# Encoder_-_error.net
KiCad netlist of a schematic drawn in Altium Designer
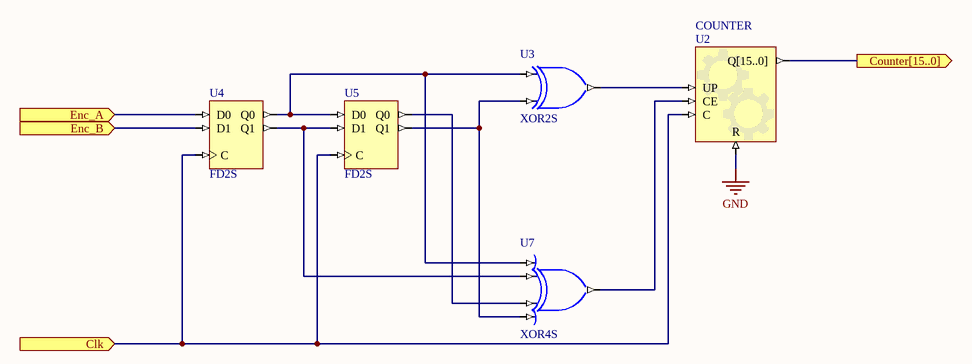
[diagram p0: Encoder - error.SchDoc]

(export (version "E")
  (design (tool "Eeschema 10.0.6"))
  (components
    (comp (ref "U2")
      (value "COUNTER")
      (description "Configurable Counter")
      (fields (field (name "PUBLISHER") "Altium Limited"))
      (libsource (lib "FPGA Configurable Generic") (part "COUNTER"))
    )
    (comp (ref "U3")
      (value "XOR2S")
      (description "2-Input Exclusive-OR Gate, Single Pin Version")
      (fields (field (name "PUBLISHER") "Altium Limited"))
      (libsource (lib "FPGA Generic") (part "XOR2S"))
    )
    (comp (ref "U4")
      (value "FD2S")
      (description "2-Bit D-Type Flip-Flop, Single Pin Version")
      (fields (field (name "PUBLISHER") "Altium Limited"))
      (libsource (lib "FPGA Generic") (part "FD2S"))
    )
    (comp (ref "U5")
      (value "FD2S")
      (description "2-Bit D-Type Flip-Flop, Single Pin Version")
      (fields (field (name "PUBLISHER") "Altium Limited"))
      (libsource (lib "FPGA Generic") (part "FD2S"))
    )
    (comp (ref "U7")
      (value "XOR4S")
      (description "4-Input Exclusive-OR Gate, Single Pin Version")
      (fields (field (name "PUBLISHER") "Altium Limited"))
      (libsource (lib "FPGA Generic") (part "XOR4S"))
    )
  )
  (nets
    (net (code "17") (name "/Clk") (class "Default")
      (node (ref "U2") (pin "C") (pinfunction "C_C") (pintype "input"))
      (node (ref "U4") (pin "C") (pinfunction "C_C") (pintype "input"))
      (node (ref "U5") (pin "C") (pinfunction "C_C") (pintype "input"))
    )
    (net (code "18") (name "/Counter[15..0]") (class "Default")
      (node (ref "U2") (pin "Q[15..0]") (pinfunction "Q[15..0]_Q[15..0]") (pintype "output"))
    )
    (net (code "19") (name "/Enc_A") (class "Default")
      (node (ref "U4") (pin "D0") (pinfunction "D0_D0") (pintype "input"))
    )
    (net (code "20") (name "/Enc_B") (class "Default")
      (node (ref "U4") (pin "D1") (pinfunction "D1_D1") (pintype "input"))
    )
    (net (code "21") (name "GND") (class "Default")
      (node (ref "U2") (pin "R") (pinfunction "R_R") (pintype "input"))
    )
    (net (code "22") (name "Net-(U2-PadCE)") (class "Default")
      (node (ref "U2") (pin "CE") (pinfunction "CE_CE") (pintype "input"))
      (node (ref "U7") (pin "O") (pinfunction "O_O") (pintype "output"))
    )
    (net (code "23") (name "Net-(U2-PadUP)") (class "Default")
      (node (ref "U2") (pin "UP") (pinfunction "UP_UP") (pintype "input"))
      (node (ref "U3") (pin "O") (pinfunction "O_O") (pintype "output"))
    )
    (net (code "24") (name "Net-(U3-PadI0)") (class "Default")
      (node (ref "U3") (pin "I0") (pinfunction "I0_I0") (pintype "input"))
      (node (ref "U4") (pin "Q0") (pinfunction "Q0_Q0") (pintype "output"))
      (node (ref "U5") (pin "D0") (pinfunction "D0_D0") (pintype "input"))
      (node (ref "U7") (pin "I0") (pinfunction "I0_I0") (pintype "input"))
    )
    (net (code "25") (name "Net-(U3-PadI1)") (class "Default")
      (node (ref "U3") (pin "I1") (pinfunction "I1_I1") (pintype "input"))
      (node (ref "U5") (pin "Q1") (pinfunction "Q1_Q1") (pintype "output"))
      (node (ref "U7") (pin "I3") (pinfunction "I3_I3") (pintype "input"))
    )
    (net (code "26") (name "Net-(U4-PadQ1)") (class "Default")
      (node (ref "U4") (pin "Q1") (pinfunction "Q1_Q1") (pintype "output"))
      (node (ref "U5") (pin "D1") (pinfunction "D1_D1") (pintype "input"))
      (node (ref "U7") (pin "I1") (pinfunction "I1_I1") (pintype "input"))
    )
    (net (code "27") (name "Net-(U5-PadQ0)") (class "Default")
      (node (ref "U5") (pin "Q0") (pinfunction "Q0_Q0") (pintype "output"))
      (node (ref "U7") (pin "I2") (pinfunction "I2_I2") (pintype "input"))
    )
  )
)
